# Power.net
KiCad netlist of a schematic drawn in Altium Designer
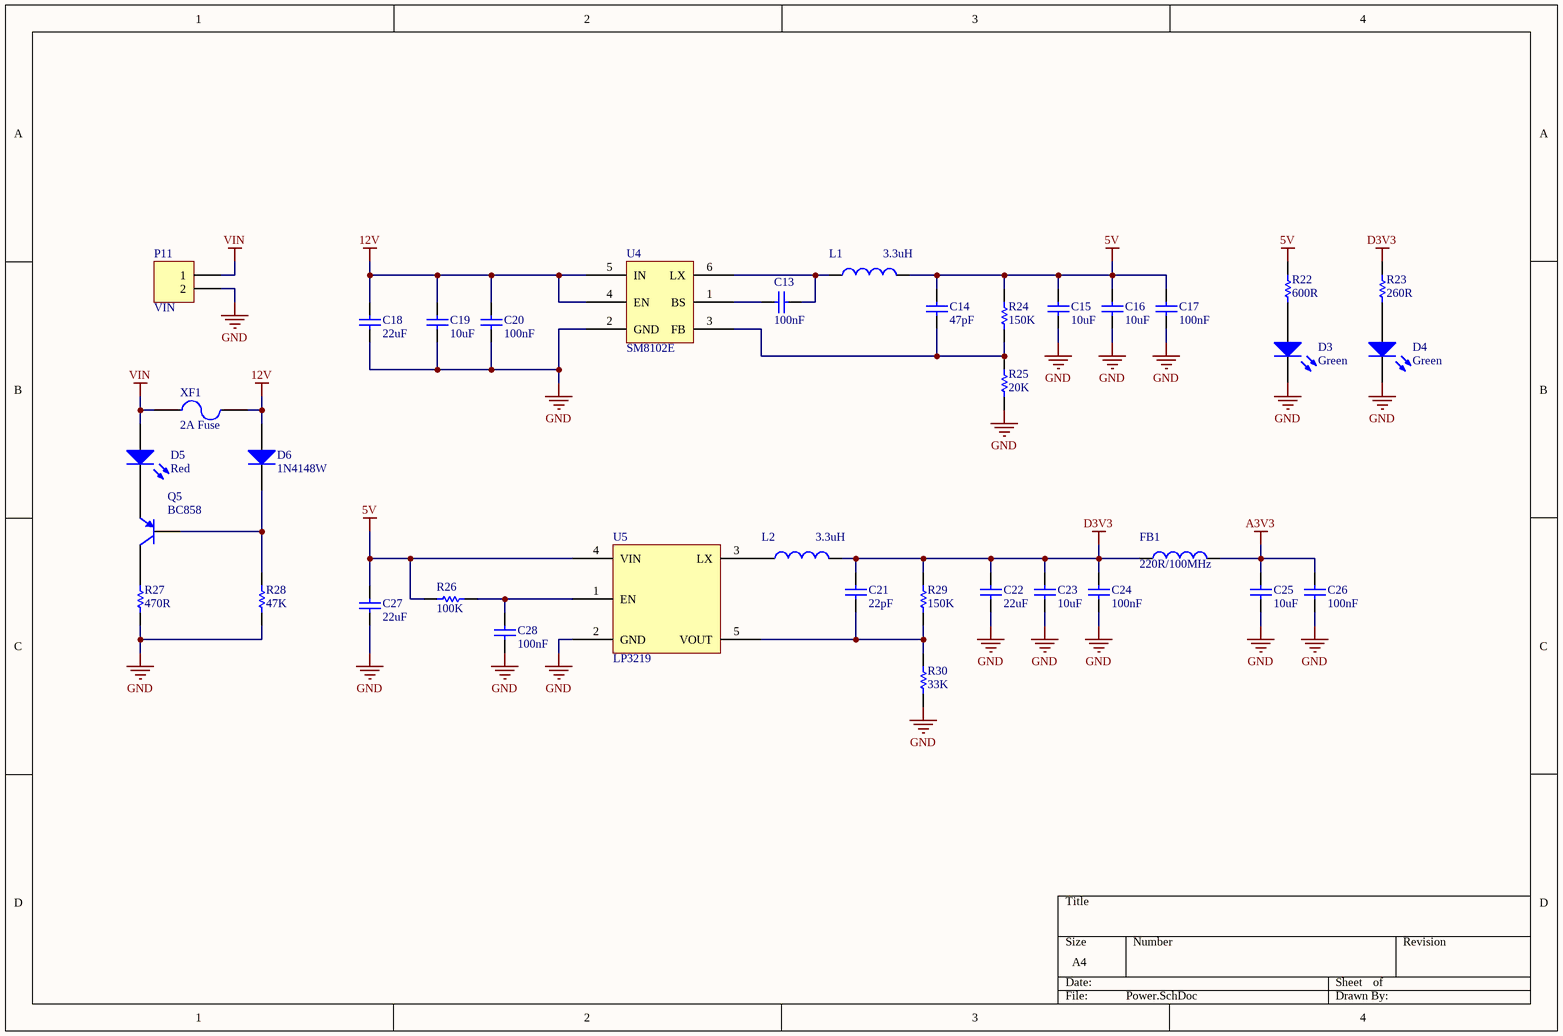
[diagram p0: Power.SchDoc]

(export (version "E")
  (design (tool "Eeschema 10.0.6"))
  (components
    (comp (ref "C13")
      (value "100nF")
      (footprint "CAP0603")
      (description "Capacitor")
      (fields (field (name "PUBLISHER") "Altium Limited"))
      (libsource (lib "Taiv") (part "Capacitor"))
    )
    (comp (ref "C14")
      (value "47pF")
      (footprint "CAP0603")
      (description "Capacitor")
      (fields (field (name "PUBLISHER") "Altium Limited"))
      (libsource (lib "Taiv") (part "Capacitor"))
    )
    (comp (ref "C15")
      (value "10uF")
      (footprint "CAP0805")
      (description "Capacitor")
      (fields (field (name "PUBLISHER") "Altium Limited"))
      (libsource (lib "Taiv") (part "Capacitor"))
    )
    (comp (ref "C16")
      (value "10uF")
      (footprint "CAP0805")
      (description "Capacitor")
      (fields (field (name "PUBLISHER") "Altium Limited"))
      (libsource (lib "Taiv") (part "Capacitor"))
    )
    (comp (ref "C17")
      (value "100nF")
      (footprint "CAP0603")
      (description "Capacitor")
      (fields (field (name "PUBLISHER") "Altium Limited"))
      (libsource (lib "Taiv") (part "Capacitor"))
    )
    (comp (ref "C18")
      (value "22uF")
      (footprint "CAP0805")
      (description "Capacitor")
      (fields (field (name "PUBLISHER") "Altium Limited"))
      (libsource (lib "Taiv") (part "Capacitor"))
    )
    (comp (ref "C19")
      (value "10uF")
      (footprint "CAP0805")
      (description "Capacitor")
      (fields (field (name "PUBLISHER") "Altium Limited"))
      (libsource (lib "Taiv") (part "Capacitor"))
    )
    (comp (ref "C20")
      (value "100nF")
      (footprint "CAP0603")
      (description "Capacitor")
      (fields (field (name "PUBLISHER") "Altium Limited"))
      (libsource (lib "Taiv") (part "Capacitor"))
    )
    (comp (ref "C21")
      (value "22pF")
      (footprint "CAP0603")
      (description "Capacitor")
      (fields (field (name "PUBLISHER") "Altium Limited"))
      (libsource (lib "Taiv") (part "Capacitor"))
    )
    (comp (ref "C22")
      (value "22uF")
      (footprint "CAP0805")
      (description "Capacitor")
      (fields (field (name "PUBLISHER") "Altium Limited"))
      (libsource (lib "Taiv") (part "Capacitor"))
    )
    (comp (ref "C23")
      (value "10uF")
      (footprint "CAP0805")
      (description "Capacitor")
      (fields (field (name "PUBLISHER") "Altium Limited"))
      (libsource (lib "Taiv") (part "Capacitor"))
    )
    (comp (ref "C24")
      (value "100nF")
      (footprint "CAP0603")
      (description "Capacitor")
      (fields (field (name "PUBLISHER") "Altium Limited"))
      (libsource (lib "Taiv") (part "Capacitor"))
    )
    (comp (ref "C25")
      (value "10uF")
      (footprint "CAP0805")
      (description "Capacitor")
      (fields (field (name "PUBLISHER") "Altium Limited"))
      (libsource (lib "Taiv") (part "Capacitor"))
    )
    (comp (ref "C26")
      (value "100nF")
      (footprint "CAP0603")
      (description "Capacitor")
      (fields (field (name "PUBLISHER") "Altium Limited"))
      (libsource (lib "Taiv") (part "Capacitor"))
    )
    (comp (ref "C27")
      (value "22uF")
      (footprint "CAP0805")
      (description "Capacitor")
      (fields (field (name "PUBLISHER") "Altium Limited"))
      (libsource (lib "Taiv") (part "Capacitor"))
    )
    (comp (ref "C28")
      (value "100nF")
      (footprint "CAP0603")
      (description "Capacitor")
      (fields (field (name "PUBLISHER") "Altium Limited"))
      (libsource (lib "Taiv") (part "Capacitor"))
    )
    (comp (ref "D3")
      (value "Green")
      (footprint "DIODE0603")
      (description "Light Emitting Diode")
      (fields (field (name "PUBLISHER") "Altium Limited"))
      (libsource (lib "Taiv") (part "LED"))
    )
    (comp (ref "D4")
      (value "Green")
      (footprint "DIODE0603")
      (description "Light Emitting Diode")
      (fields (field (name "PUBLISHER") "Altium Limited"))
      (libsource (lib "Taiv") (part "LED"))
    )
    (comp (ref "D5")
      (value "Red")
      (footprint "DIODE0603")
      (description "Light Emitting Diode")
      (fields (field (name "PUBLISHER") "Altium Limited"))
      (libsource (lib "Taiv") (part "LED"))
    )
    (comp (ref "D6")
      (value "1N4148W")
      (footprint "SOD-123")
      (description "Diode")
      (libsource (lib "Taiv") (part "Diode"))
    )
    (comp (ref "FB1")
      (value "220R/100MHz")
      (footprint "IND0603")
      (description "Ferrite Bead")
      (fields (field (name "PUBLISHER") "Altium Limited"))
      (libsource (lib "Taiv") (part "Inductor"))
    )
    (comp (ref "L1")
      (value "3.3uH")
      (footprint "IND4x4x1.8")
      (description "Inductor")
      (fields (field (name "PUBLISHER") "Altium Limited"))
      (libsource (lib "Miscellaneous Devices") (part "Inductor"))
    )
    (comp (ref "L2")
      (value "3.3uH")
      (footprint "IND4x4x1.8")
      (description "Inductor")
      (fields (field (name "PUBLISHER") "Altium Limited"))
      (libsource (lib "Miscellaneous Devices") (part "Inductor"))
    )
    (comp (ref "P11")
      (value "VIN")
      (footprint "SCREW TERMINAL 5MM")
      (description "Header, 2-Pin")
      (fields (field (name "PUBLISHER") "Altium Limited"))
      (libsource (lib "Taiv") (part "2X1 2.54MM"))
    )
    (comp (ref "Q5")
      (value "BC858")
      (footprint "SOT-23")
      (description "PNP Bipolar Transistor")
      (fields (field (name "PUBLISHER") "Altium Limited"))
      (libsource (lib "Taiv") (part "PNP"))
    )
    (comp (ref "R22")
      (value "600R")
      (footprint "RES0603")
      (description "Resistor")
      (fields (field (name "PUBLISHER") "Altium Limited"))
      (libsource (lib "Taiv") (part "Resistor"))
    )
    (comp (ref "R23")
      (value "260R")
      (footprint "RES0603")
      (description "Resistor")
      (fields (field (name "PUBLISHER") "Altium Limited"))
      (libsource (lib "Taiv") (part "Resistor"))
    )
    (comp (ref "R24")
      (value "150K")
      (footprint "RES0603")
      (description "Resistor")
      (fields (field (name "PUBLISHER") "Altium Limited"))
      (libsource (lib "Taiv") (part "Resistor"))
    )
    (comp (ref "R25")
      (value "20K")
      (footprint "RES0603")
      (description "Resistor")
      (fields (field (name "PUBLISHER") "Altium Limited"))
      (libsource (lib "Taiv") (part "Resistor"))
    )
    (comp (ref "R26")
      (value "100K")
      (footprint "RES0603")
      (description "Resistor")
      (fields (field (name "PUBLISHER") "Altium Limited"))
      (libsource (lib "Taiv") (part "Resistor"))
    )
    (comp (ref "R27")
      (value "470R")
      (footprint "RES0603")
      (description "Resistor")
      (fields (field (name "PUBLISHER") "Altium Limited"))
      (libsource (lib "Taiv") (part "Resistor"))
    )
    (comp (ref "R28")
      (value "47K")
      (footprint "RES0603")
      (description "Resistor")
      (fields (field (name "PUBLISHER") "Altium Limited"))
      (libsource (lib "Taiv") (part "Resistor"))
    )
    (comp (ref "R29")
      (value "150K")
      (footprint "RES0603")
      (description "Resistor")
      (fields (field (name "PUBLISHER") "Altium Limited"))
      (libsource (lib "Taiv") (part "Resistor"))
    )
    (comp (ref "R30")
      (value "33K")
      (footprint "RES0603")
      (description "Resistor")
      (fields (field (name "PUBLISHER") "Altium Limited"))
      (libsource (lib "Taiv") (part "Resistor"))
    )
    (comp (ref "U4")
      (value "SM8102E")
      (footprint "SOT-23-6")
      (description "Adjustable VREG")
      (libsource (lib "TaivV2") (part "SM8102E"))
    )
    (comp (ref "U5")
      (value "LP3219")
      (footprint "SOT-23-5")
      (description "ADJ 1.5A buck convertor")
      (libsource (lib "TaivV2") (part "LP3219"))
    )
    (comp (ref "XF1")
      (value "2A Fuse")
      (footprint "ATO Fuse Holder SMD")
      (description "Automotive Fuse Holder")
      (libsource (lib "Taiv") (part "ATO Fuse Holder"))
    )
  )
  (nets
    (net (code "1") (name "5V") (class "Default")
      (node (ref "C14") (pin "2") (pinfunction "2_2") (pintype "passive"))
      (node (ref "C15") (pin "2") (pinfunction "2_2") (pintype "passive"))
      (node (ref "C16") (pin "2") (pinfunction "2_2") (pintype "passive"))
      (node (ref "C17") (pin "2") (pinfunction "2_2") (pintype "passive"))
      (node (ref "C27") (pin "2") (pinfunction "2_2") (pintype "passive"))
      (node (ref "L1") (pin "2") (pinfunction "2_2") (pintype "passive"))
      (node (ref "R22") (pin "2") (pinfunction "2_2") (pintype "passive"))
      (node (ref "R24") (pin "2") (pinfunction "2_2") (pintype "passive"))
      (node (ref "R26") (pin "2") (pinfunction "2_2") (pintype "passive"))
      (node (ref "U5") (pin "4") (pinfunction "VIN_4") (pintype "passive"))
    )
    (net (code "2") (name "12V") (class "Default")
      (node (ref "C18") (pin "2") (pinfunction "2_2") (pintype "passive"))
      (node (ref "C19") (pin "2") (pinfunction "2_2") (pintype "passive"))
      (node (ref "C20") (pin "2") (pinfunction "2_2") (pintype "passive"))
      (node (ref "D6") (pin "1") (pinfunction "A_1") (pintype "passive"))
      (node (ref "U4") (pin "4") (pinfunction "EN_4") (pintype "passive"))
      (node (ref "U4") (pin "5") (pinfunction "IN_5") (pintype "passive"))
      (node (ref "XF1") (pin "2") (pinfunction "2_2") (pintype "passive"))
    )
    (net (code "3") (name "A3V3") (class "Default")
      (node (ref "C25") (pin "2") (pinfunction "2_2") (pintype "passive"))
      (node (ref "C26") (pin "2") (pinfunction "2_2") (pintype "passive"))
      (node (ref "FB1") (pin "2") (pinfunction "2_2") (pintype "passive"))
    )
    (net (code "4") (name "D3V3") (class "Default")
      (node (ref "C21") (pin "2") (pinfunction "2_2") (pintype "passive"))
      (node (ref "C22") (pin "2") (pinfunction "2_2") (pintype "passive"))
      (node (ref "C23") (pin "2") (pinfunction "2_2") (pintype "passive"))
      (node (ref "C24") (pin "2") (pinfunction "2_2") (pintype "passive"))
      (node (ref "FB1") (pin "1") (pinfunction "1_1") (pintype "passive"))
      (node (ref "L2") (pin "2") (pinfunction "2_2") (pintype "passive"))
      (node (ref "R23") (pin "2") (pinfunction "2_2") (pintype "passive"))
      (node (ref "R29") (pin "2") (pinfunction "2_2") (pintype "passive"))
    )
    (net (code "5") (name "GND") (class "Default")
      (node (ref "C15") (pin "1") (pinfunction "1_1") (pintype "passive"))
      (node (ref "C16") (pin "1") (pinfunction "1_1") (pintype "passive"))
      (node (ref "C17") (pin "1") (pinfunction "1_1") (pintype "passive"))
      (node (ref "C18") (pin "1") (pinfunction "1_1") (pintype "passive"))
      (node (ref "C19") (pin "1") (pinfunction "1_1") (pintype "passive"))
      (node (ref "C20") (pin "1") (pinfunction "1_1") (pintype "passive"))
      (node (ref "C22") (pin "1") (pinfunction "1_1") (pintype "passive"))
      (node (ref "C23") (pin "1") (pinfunction "1_1") (pintype "passive"))
      (node (ref "C24") (pin "1") (pinfunction "1_1") (pintype "passive"))
      (node (ref "C25") (pin "1") (pinfunction "1_1") (pintype "passive"))
      (node (ref "C26") (pin "1") (pinfunction "1_1") (pintype "passive"))
      (node (ref "C27") (pin "1") (pinfunction "1_1") (pintype "passive"))
      (node (ref "C28") (pin "1") (pinfunction "1_1") (pintype "passive"))
      (node (ref "D3") (pin "2") (pinfunction "K_2") (pintype "passive"))
      (node (ref "D4") (pin "2") (pinfunction "K_2") (pintype "passive"))
      (node (ref "P11") (pin "2") (pinfunction "2_2") (pintype "passive"))
      (node (ref "R25") (pin "1") (pinfunction "1_1") (pintype "passive"))
      (node (ref "R27") (pin "1") (pinfunction "1_1") (pintype "passive"))
      (node (ref "R28") (pin "1") (pinfunction "1_1") (pintype "passive"))
      (node (ref "R30") (pin "1") (pinfunction "1_1") (pintype "passive"))
      (node (ref "U4") (pin "2") (pinfunction "GND_2") (pintype "passive"))
      (node (ref "U5") (pin "2") (pinfunction "GND_2") (pintype "passive"))
    )
    (net (code "6") (name "Net-(D3-A)") (class "Default")
      (node (ref "D3") (pin "1") (pinfunction "A_1") (pintype "passive"))
      (node (ref "R22") (pin "1") (pinfunction "1_1") (pintype "passive"))
    )
    (net (code "7") (name "Net-(D4-A)") (class "Default")
      (node (ref "D4") (pin "1") (pinfunction "A_1") (pintype "passive"))
      (node (ref "R23") (pin "1") (pinfunction "1_1") (pintype "passive"))
    )
    (net (code "8") (name "Net-(D5-K)") (class "Default")
      (node (ref "D5") (pin "2") (pinfunction "K_2") (pintype "passive"))
      (node (ref "Q5") (pin "2") (pinfunction "E_2") (pintype "passive"))
    )
    (net (code "9") (name "Net-(D6-K)") (class "Default")
      (node (ref "D6") (pin "2") (pinfunction "K_2") (pintype "passive"))
      (node (ref "Q5") (pin "1") (pinfunction "B_1") (pintype "passive"))
      (node (ref "R28") (pin "2") (pinfunction "2_2") (pintype "passive"))
    )
    (net (code "10") (name "Net-(Q5-C)") (class "Default")
      (node (ref "Q5") (pin "3") (pinfunction "C_3") (pintype "passive"))
      (node (ref "R27") (pin "2") (pinfunction "2_2") (pintype "passive"))
    )
    (net (code "11") (name "Net-(U4-BS)") (class "Default")
      (node (ref "C13") (pin "2") (pinfunction "2_2") (pintype "passive"))
      (node (ref "U4") (pin "1") (pinfunction "BS_1") (pintype "passive"))
    )
    (net (code "12") (name "Net-(U4-FB)") (class "Default")
      (node (ref "C14") (pin "1") (pinfunction "1_1") (pintype "passive"))
      (node (ref "R24") (pin "1") (pinfunction "1_1") (pintype "passive"))
      (node (ref "R25") (pin "2") (pinfunction "2_2") (pintype "passive"))
      (node (ref "U4") (pin "3") (pinfunction "FB_3") (pintype "passive"))
    )
    (net (code "13") (name "Net-(U4-LX)") (class "Default")
      (node (ref "C13") (pin "1") (pinfunction "1_1") (pintype "passive"))
      (node (ref "L1") (pin "1") (pinfunction "1_1") (pintype "passive"))
      (node (ref "U4") (pin "6") (pinfunction "LX_6") (pintype "passive"))
    )
    (net (code "14") (name "Net-(U5-EN)") (class "Default")
      (node (ref "C28") (pin "2") (pinfunction "2_2") (pintype "passive"))
      (node (ref "R26") (pin "1") (pinfunction "1_1") (pintype "passive"))
      (node (ref "U5") (pin "1") (pinfunction "EN_1") (pintype "passive"))
    )
    (net (code "15") (name "Net-(U5-LX)") (class "Default")
      (node (ref "L2") (pin "1") (pinfunction "1_1") (pintype "passive"))
      (node (ref "U5") (pin "3") (pinfunction "LX_3") (pintype "passive"))
    )
    (net (code "16") (name "Net-(U5-VOUT)") (class "Default")
      (node (ref "C21") (pin "1") (pinfunction "1_1") (pintype "passive"))
      (node (ref "R29") (pin "1") (pinfunction "1_1") (pintype "passive"))
      (node (ref "R30") (pin "2") (pinfunction "2_2") (pintype "passive"))
      (node (ref "U5") (pin "5") (pinfunction "VOUT_5") (pintype "passive"))
    )
    (net (code "17") (name "VIN") (class "Default")
      (node (ref "D5") (pin "1") (pinfunction "A_1") (pintype "passive"))
      (node (ref "P11") (pin "1") (pinfunction "1_1") (pintype "passive"))
      (node (ref "XF1") (pin "1") (pinfunction "1_1") (pintype "passive"))
    )
  )
)
